# 01_ZYNQ_DDR.net
KiCad netlist of a schematic drawn in Altium Designer
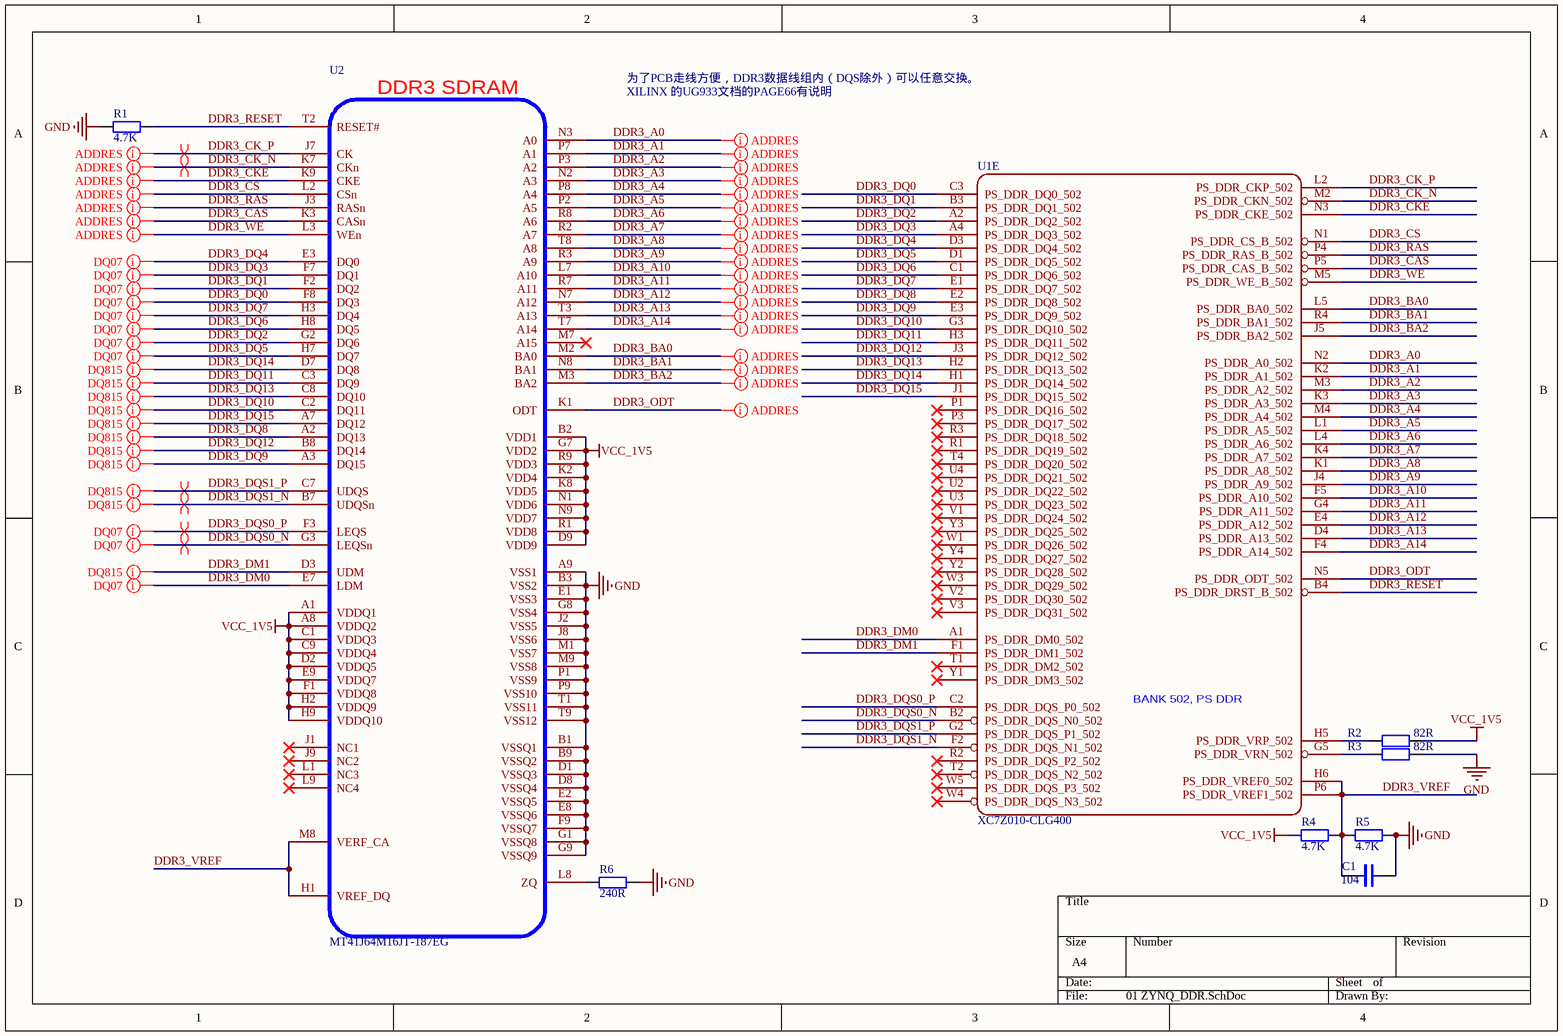
[diagram p0: 01 ZYNQ_DDR.SchDoc]

(export (version "E")
  (design (tool "Eeschema 10.0.6"))
  (components
    (comp (ref "C1")
      (value "104")
      (footprint "LC-0402_C")
      (description "Capacitor")
      (libsource (lib "General") (part "CAP"))
    )
    (comp (ref "R1")
      (value "4.7K")
      (footprint "LC-0402_R")
      (description "Resistor")
      (libsource (lib "General") (part "RES"))
    )
    (comp (ref "R2")
      (value "82R")
      (footprint "LC-0402_R")
      (description "Resistor")
      (libsource (lib "General") (part "RES"))
    )
    (comp (ref "R3")
      (value "82R")
      (footprint "LC-0402_R")
      (description "Resistor")
      (libsource (lib "General") (part "RES"))
    )
    (comp (ref "R4")
      (value "4.7K")
      (footprint "LC-0402_R")
      (description "Resistor")
      (libsource (lib "General") (part "RES"))
    )
    (comp (ref "R5")
      (value "4.7K")
      (footprint "LC-0402_R")
      (description "Resistor")
      (libsource (lib "General") (part "RES"))
    )
    (comp (ref "R6")
      (value "240R")
      (footprint "LC-0402_R")
      (description "Resistor")
      (libsource (lib "") (part "RES_1"))
    )
    (comp (ref "U1")
      (value "XC7Z010-CLG400")
      (footprint "CLG400-0.8")
      (libsource (lib "DDR3_xc7z010-clg400") (part "XC7Z010-CLG400"))
    )
    (comp (ref "U2")
      (value "MT41J64M16JT-187EG")
      (footprint "FBGA96")
      (libsource (lib "DDR3_xc7z010-clg400") (part "DDR3"))
    )
  )
  (nets
    (net (code "1") (name "/DDR3_A0") (class "Default")
      (node (ref "U1") (pin "N2") (pinfunction "PS_DDR_A0_502_N2") (pintype "passive"))
      (node (ref "U2") (pin "N3") (pinfunction "A0_N3") (pintype "passive"))
    )
    (net (code "2") (name "/DDR3_A1") (class "Default")
      (node (ref "U1") (pin "K2") (pinfunction "PS_DDR_A1_502_K2") (pintype "passive"))
      (node (ref "U2") (pin "P7") (pinfunction "A1_P7") (pintype "passive"))
    )
    (net (code "3") (name "/DDR3_A2") (class "Default")
      (node (ref "U1") (pin "M3") (pinfunction "PS_DDR_A2_502_M3") (pintype "passive"))
      (node (ref "U2") (pin "P3") (pinfunction "A2_P3") (pintype "passive"))
    )
    (net (code "4") (name "/DDR3_A3") (class "Default")
      (node (ref "U1") (pin "K3") (pinfunction "PS_DDR_A3_502_K3") (pintype "passive"))
      (node (ref "U2") (pin "N2") (pinfunction "A3_N2") (pintype "passive"))
    )
    (net (code "5") (name "/DDR3_A4") (class "Default")
      (node (ref "U1") (pin "M4") (pinfunction "PS_DDR_A4_502_M4") (pintype "passive"))
      (node (ref "U2") (pin "P8") (pinfunction "A4_P8") (pintype "passive"))
    )
    (net (code "6") (name "/DDR3_A5") (class "Default")
      (node (ref "U1") (pin "L1") (pinfunction "PS_DDR_A5_502_L1") (pintype "passive"))
      (node (ref "U2") (pin "P2") (pinfunction "A5_P2") (pintype "passive"))
    )
    (net (code "7") (name "/DDR3_A6") (class "Default")
      (node (ref "U1") (pin "L4") (pinfunction "PS_DDR_A6_502_L4") (pintype "passive"))
      (node (ref "U2") (pin "R8") (pinfunction "A6_R8") (pintype "passive"))
    )
    (net (code "8") (name "/DDR3_A7") (class "Default")
      (node (ref "U1") (pin "K4") (pinfunction "PS_DDR_A7_502_K4") (pintype "passive"))
      (node (ref "U2") (pin "R2") (pinfunction "A7_R2") (pintype "passive"))
    )
    (net (code "9") (name "/DDR3_A8") (class "Default")
      (node (ref "U1") (pin "K1") (pinfunction "PS_DDR_A8_502_K1") (pintype "passive"))
      (node (ref "U2") (pin "T8") (pinfunction "A8_T8") (pintype "passive"))
    )
    (net (code "10") (name "/DDR3_A9") (class "Default")
      (node (ref "U1") (pin "J4") (pinfunction "PS_DDR_A9_502_J4") (pintype "passive"))
      (node (ref "U2") (pin "R3") (pinfunction "A9_R3") (pintype "passive"))
    )
    (net (code "11") (name "/DDR3_A10") (class "Default")
      (node (ref "U1") (pin "F5") (pinfunction "PS_DDR_A10_502_F5") (pintype "passive"))
      (node (ref "U2") (pin "L7") (pinfunction "A10_L7") (pintype "passive"))
    )
    (net (code "12") (name "/DDR3_A11") (class "Default")
      (node (ref "U1") (pin "G4") (pinfunction "PS_DDR_A11_502_G4") (pintype "passive"))
      (node (ref "U2") (pin "R7") (pinfunction "A11_R7") (pintype "passive"))
    )
    (net (code "13") (name "/DDR3_A12") (class "Default")
      (node (ref "U1") (pin "E4") (pinfunction "PS_DDR_A12_502_E4") (pintype "passive"))
      (node (ref "U2") (pin "N7") (pinfunction "A12_N7") (pintype "passive"))
    )
    (net (code "14") (name "/DDR3_A13") (class "Default")
      (node (ref "U1") (pin "D4") (pinfunction "PS_DDR_A13_502_D4") (pintype "passive"))
      (node (ref "U2") (pin "T3") (pinfunction "A13_T3") (pintype "passive"))
    )
    (net (code "15") (name "/DDR3_A14") (class "Default")
      (node (ref "U1") (pin "F4") (pinfunction "PS_DDR_A14_502_F4") (pintype "passive"))
      (node (ref "U2") (pin "T7") (pinfunction "A14_T7") (pintype "passive"))
    )
    (net (code "16") (name "/DDR3_BA0") (class "Default")
      (node (ref "U1") (pin "L5") (pinfunction "PS_DDR_BA0_502_L5") (pintype "passive"))
      (node (ref "U2") (pin "M2") (pinfunction "BA0_M2") (pintype "passive"))
    )
    (net (code "17") (name "/DDR3_BA1") (class "Default")
      (node (ref "U1") (pin "R4") (pinfunction "PS_DDR_BA1_502_R4") (pintype "passive"))
      (node (ref "U2") (pin "N8") (pinfunction "BA1_N8") (pintype "passive"))
    )
    (net (code "18") (name "/DDR3_BA2") (class "Default")
      (node (ref "U1") (pin "J5") (pinfunction "PS_DDR_BA2_502_J5") (pintype "passive"))
      (node (ref "U2") (pin "M3") (pinfunction "BA2_M3") (pintype "passive"))
    )
    (net (code "19") (name "/DDR3_CAS") (class "Default")
      (node (ref "U1") (pin "P5") (pinfunction "PS_DDR_CAS_B_502_P5") (pintype "passive"))
      (node (ref "U2") (pin "K3") (pinfunction "CASn_K3") (pintype "passive"))
    )
    (net (code "20") (name "/DDR3_CKE") (class "Default")
      (node (ref "U1") (pin "N3") (pinfunction "PS_DDR_CKE_502_N3") (pintype "passive"))
      (node (ref "U2") (pin "K9") (pinfunction "CKE_K9") (pintype "passive"))
    )
    (net (code "21") (name "/DDR3_CK_N") (class "Default")
      (node (ref "U1") (pin "M2") (pinfunction "PS_DDR_CKN_502_M2") (pintype "passive"))
      (node (ref "U2") (pin "K7") (pinfunction "CKn_K7") (pintype "passive"))
    )
    (net (code "22") (name "/DDR3_CK_P") (class "Default")
      (node (ref "U1") (pin "L2") (pinfunction "PS_DDR_CKP_502_L2") (pintype "passive"))
      (node (ref "U2") (pin "J7") (pinfunction "CK_J7") (pintype "passive"))
    )
    (net (code "23") (name "/DDR3_CS") (class "Default")
      (node (ref "U1") (pin "N1") (pinfunction "PS_DDR_CS_B_502_N1") (pintype "passive"))
      (node (ref "U2") (pin "L2") (pinfunction "CSn_L2") (pintype "passive"))
    )
    (net (code "24") (name "/DDR3_DM0") (class "Default")
      (node (ref "U1") (pin "A1") (pinfunction "PS_DDR_DM0_502_A1") (pintype "passive"))
      (node (ref "U2") (pin "E7") (pinfunction "LDM_E7") (pintype "passive"))
    )
    (net (code "25") (name "/DDR3_DM1") (class "Default")
      (node (ref "U1") (pin "F1") (pinfunction "PS_DDR_DM1_502_F1") (pintype "passive"))
      (node (ref "U2") (pin "D3") (pinfunction "UDM_D3") (pintype "passive"))
    )
    (net (code "26") (name "/DDR3_DQ0") (class "Default")
      (node (ref "U1") (pin "C3") (pinfunction "PS_DDR_DQ0_502_C3") (pintype "passive"))
      (node (ref "U2") (pin "F8") (pinfunction "DQ3_F8") (pintype "passive"))
    )
    (net (code "27") (name "/DDR3_DQ1") (class "Default")
      (node (ref "U1") (pin "B3") (pinfunction "PS_DDR_DQ1_502_B3") (pintype "passive"))
      (node (ref "U2") (pin "F2") (pinfunction "DQ2_F2") (pintype "passive"))
    )
    (net (code "28") (name "/DDR3_DQ2") (class "Default")
      (node (ref "U1") (pin "A2") (pinfunction "PS_DDR_DQ2_502_A2") (pintype "passive"))
      (node (ref "U2") (pin "G2") (pinfunction "DQ6_G2") (pintype "passive"))
    )
    (net (code "29") (name "/DDR3_DQ3") (class "Default")
      (node (ref "U1") (pin "A4") (pinfunction "PS_DDR_DQ3_502_A4") (pintype "passive"))
      (node (ref "U2") (pin "F7") (pinfunction "DQ1_F7") (pintype "passive"))
    )
    (net (code "30") (name "/DDR3_DQ4") (class "Default")
      (node (ref "U1") (pin "D3") (pinfunction "PS_DDR_DQ4_502_D3") (pintype "passive"))
      (node (ref "U2") (pin "E3") (pinfunction "DQ0_E3") (pintype "passive"))
    )
    (net (code "31") (name "/DDR3_DQ5") (class "Default")
      (node (ref "U1") (pin "D1") (pinfunction "PS_DDR_DQ5_502_D1") (pintype "passive"))
      (node (ref "U2") (pin "H7") (pinfunction "DQ7_H7") (pintype "passive"))
    )
    (net (code "32") (name "/DDR3_DQ6") (class "Default")
      (node (ref "U1") (pin "C1") (pinfunction "PS_DDR_DQ6_502_C1") (pintype "passive"))
      (node (ref "U2") (pin "H8") (pinfunction "DQ5_H8") (pintype "passive"))
    )
    (net (code "33") (name "/DDR3_DQ7") (class "Default")
      (node (ref "U1") (pin "E1") (pinfunction "PS_DDR_DQ7_502_E1") (pintype "passive"))
      (node (ref "U2") (pin "H3") (pinfunction "DQ4_H3") (pintype "passive"))
    )
    (net (code "34") (name "/DDR3_DQ8") (class "Default")
      (node (ref "U1") (pin "E2") (pinfunction "PS_DDR_DQ8_502_E2") (pintype "passive"))
      (node (ref "U2") (pin "A2") (pinfunction "DQ13_A2") (pintype "passive"))
    )
    (net (code "35") (name "/DDR3_DQ9") (class "Default")
      (node (ref "U1") (pin "E3") (pinfunction "PS_DDR_DQ9_502_E3") (pintype "passive"))
      (node (ref "U2") (pin "A3") (pinfunction "DQ15_A3") (pintype "passive"))
    )
    (net (code "36") (name "/DDR3_DQ10") (class "Default")
      (node (ref "U1") (pin "G3") (pinfunction "PS_DDR_DQ10_502_G3") (pintype "passive"))
      (node (ref "U2") (pin "C2") (pinfunction "DQ11_C2") (pintype "passive"))
    )
    (net (code "37") (name "/DDR3_DQ11") (class "Default")
      (node (ref "U1") (pin "H3") (pinfunction "PS_DDR_DQ11_502_H3") (pintype "passive"))
      (node (ref "U2") (pin "C3") (pinfunction "DQ9_C3") (pintype "passive"))
    )
    (net (code "38") (name "/DDR3_DQ12") (class "Default")
      (node (ref "U1") (pin "J3") (pinfunction "PS_DDR_DQ12_502_J3") (pintype "passive"))
      (node (ref "U2") (pin "B8") (pinfunction "DQ14_B8") (pintype "passive"))
    )
    (net (code "39") (name "/DDR3_DQ13") (class "Default")
      (node (ref "U1") (pin "H2") (pinfunction "PS_DDR_DQ13_502_H2") (pintype "passive"))
      (node (ref "U2") (pin "C8") (pinfunction "DQ10_C8") (pintype "passive"))
    )
    (net (code "40") (name "/DDR3_DQ14") (class "Default")
      (node (ref "U1") (pin "H1") (pinfunction "PS_DDR_DQ14_502_H1") (pintype "passive"))
      (node (ref "U2") (pin "D7") (pinfunction "DQ8_D7") (pintype "passive"))
    )
    (net (code "41") (name "/DDR3_DQ15") (class "Default")
      (node (ref "U1") (pin "J1") (pinfunction "PS_DDR_DQ15_502_J1") (pintype "passive"))
      (node (ref "U2") (pin "A7") (pinfunction "DQ12_A7") (pintype "passive"))
    )
    (net (code "42") (name "/DDR3_DQS0_N") (class "Default")
      (node (ref "U1") (pin "B2") (pinfunction "PS_DDR_DQS_N0_502_B2") (pintype "passive"))
      (node (ref "U2") (pin "G3") (pinfunction "LEQSn_G3") (pintype "passive"))
    )
    (net (code "43") (name "/DDR3_DQS0_P") (class "Default")
      (node (ref "U1") (pin "C2") (pinfunction "PS_DDR_DQS_P0_502_C2") (pintype "passive"))
      (node (ref "U2") (pin "F3") (pinfunction "LEQS_F3") (pintype "passive"))
    )
    (net (code "44") (name "/DDR3_DQS1_N") (class "Default")
      (node (ref "U1") (pin "F2") (pinfunction "PS_DDR_DQS_N1_502_F2") (pintype "passive"))
      (node (ref "U2") (pin "B7") (pinfunction "UDQSn_B7") (pintype "passive"))
    )
    (net (code "45") (name "/DDR3_DQS1_P") (class "Default")
      (node (ref "U1") (pin "G2") (pinfunction "PS_DDR_DQS_P1_502_G2") (pintype "passive"))
      (node (ref "U2") (pin "C7") (pinfunction "UDQS_C7") (pintype "passive"))
    )
    (net (code "46") (name "/DDR3_ODT") (class "Default")
      (node (ref "U1") (pin "N5") (pinfunction "PS_DDR_ODT_502_N5") (pintype "passive"))
      (node (ref "U2") (pin "K1") (pinfunction "ODT_K1") (pintype "passive"))
    )
    (net (code "47") (name "/DDR3_RAS") (class "Default")
      (node (ref "U1") (pin "P4") (pinfunction "PS_DDR_RAS_B_502_P4") (pintype "passive"))
      (node (ref "U2") (pin "J3") (pinfunction "RASn_J3") (pintype "passive"))
    )
    (net (code "48") (name "/DDR3_RESET") (class "Default")
      (node (ref "R1") (pin "1") (pinfunction "1_1") (pintype "passive"))
      (node (ref "U1") (pin "B4") (pinfunction "PS_DDR_DRST_B_502_B4") (pintype "passive"))
      (node (ref "U2") (pin "T2") (pinfunction "RESET#_T2") (pintype "passive"))
    )
    (net (code "49") (name "/DDR3_VREF") (class "Default")
      (node (ref "C1") (pin "1") (pinfunction "1_1") (pintype "passive"))
      (node (ref "R4") (pin "1") (pinfunction "1_1") (pintype "passive"))
      (node (ref "R5") (pin "2") (pinfunction "2_2") (pintype "passive"))
      (node (ref "U1") (pin "H6") (pinfunction "PS_DDR_VREF0_502_H6") (pintype "passive"))
      (node (ref "U1") (pin "P6") (pinfunction "PS_DDR_VREF1_502_P6") (pintype "passive"))
      (node (ref "U2") (pin "H1") (pinfunction "VREF_DQ_H1") (pintype "passive"))
      (node (ref "U2") (pin "M8") (pinfunction "VERF_CA_M8") (pintype "passive"))
    )
    (net (code "50") (name "/DDR3_WE") (class "Default")
      (node (ref "U1") (pin "M5") (pinfunction "PS_DDR_WE_B_502_M5") (pintype "passive"))
      (node (ref "U2") (pin "L3") (pinfunction "WEn_L3") (pintype "passive"))
    )
    (net (code "51") (name "GND") (class "Default")
      (node (ref "C1") (pin "2") (pinfunction "2_2") (pintype "passive"))
      (node (ref "R1") (pin "2") (pinfunction "2_2") (pintype "passive"))
      (node (ref "R3") (pin "1") (pinfunction "1_1") (pintype "passive"))
      (node (ref "R5") (pin "1") (pinfunction "1_1") (pintype "passive"))
      (node (ref "R6") (pin "2") (pinfunction "2_2") (pintype "passive"))
      (node (ref "U2") (pin "A9") (pinfunction "VSS1_A9") (pintype "passive"))
      (node (ref "U2") (pin "B1") (pinfunction "VSSQ1_B1") (pintype "passive"))
      (node (ref "U2") (pin "B3") (pinfunction "VSS2_B3") (pintype "passive"))
      (node (ref "U2") (pin "B9") (pinfunction "VSSQ2_B9") (pintype "passive"))
      (node (ref "U2") (pin "D1") (pinfunction "VSSQ3_D1") (pintype "passive"))
      (node (ref "U2") (pin "D8") (pinfunction "VSSQ4_D8") (pintype "passive"))
      (node (ref "U2") (pin "E1") (pinfunction "VSS3_E1") (pintype "passive"))
      (node (ref "U2") (pin "E2") (pinfunction "VSSQ5_E2") (pintype "passive"))
      (node (ref "U2") (pin "E8") (pinfunction "VSSQ6_E8") (pintype "passive"))
      (node (ref "U2") (pin "F9") (pinfunction "VSSQ7_F9") (pintype "passive"))
      (node (ref "U2") (pin "G1") (pinfunction "VSSQ8_G1") (pintype "passive"))
      (node (ref "U2") (pin "G8") (pinfunction "VSS4_G8") (pintype "passive"))
      (node (ref "U2") (pin "G9") (pinfunction "VSSQ9_G9") (pintype "passive"))
      (node (ref "U2") (pin "J2") (pinfunction "VSS5_J2") (pintype "passive"))
      (node (ref "U2") (pin "J8") (pinfunction "VSS6_J8") (pintype "passive"))
      (node (ref "U2") (pin "M1") (pinfunction "VSS7_M1") (pintype "passive"))
      (node (ref "U2") (pin "M9") (pinfunction "VSS8_M9") (pintype "passive"))
      (node (ref "U2") (pin "P1") (pinfunction "VSS9_P1") (pintype "passive"))
      (node (ref "U2") (pin "P9") (pinfunction "VSS10_P9") (pintype "passive"))
      (node (ref "U2") (pin "T1") (pinfunction "VSS11_T1") (pintype "passive"))
      (node (ref "U2") (pin "T9") (pinfunction "VSS12_T9") (pintype "passive"))
    )
    (net (code "52") (name "Net-(U1E-PS_DDR_VRN_502)") (class "Default")
      (node (ref "R3") (pin "2") (pinfunction "2_2") (pintype "passive"))
      (node (ref "U1") (pin "G5") (pinfunction "PS_DDR_VRN_502_G5") (pintype "passive"))
    )
    (net (code "53") (name "Net-(U1E-PS_DDR_VRP_502)") (class "Default")
      (node (ref "R2") (pin "2") (pinfunction "2_2") (pintype "passive"))
      (node (ref "U1") (pin "H5") (pinfunction "PS_DDR_VRP_502_H5") (pintype "passive"))
    )
    (net (code "54") (name "Net-(U2-ZQ)") (class "Default")
      (node (ref "R6") (pin "1") (pinfunction "1_1") (pintype "passive"))
      (node (ref "U2") (pin "L8") (pinfunction "ZQ_L8") (pintype "passive"))
    )
    (net (code "55") (name "VCC_1V5") (class "Default")
      (node (ref "R2") (pin "1") (pinfunction "1_1") (pintype "passive"))
      (node (ref "R4") (pin "2") (pinfunction "2_2") (pintype "passive"))
      (node (ref "U2") (pin "A1") (pinfunction "VDDQ1_A1") (pintype "passive"))
      (node (ref "U2") (pin "A8") (pinfunction "VDDQ2_A8") (pintype "passive"))
      (node (ref "U2") (pin "B2") (pinfunction "VDD1_B2") (pintype "passive"))
      (node (ref "U2") (pin "C1") (pinfunction "VDDQ3_C1") (pintype "passive"))
      (node (ref "U2") (pin "C9") (pinfunction "VDDQ4_C9") (pintype "passive"))
      (node (ref "U2") (pin "D2") (pinfunction "VDDQ5_D2") (pintype "passive"))
      (node (ref "U2") (pin "D9") (pinfunction "VDD9_D9") (pintype "passive"))
      (node (ref "U2") (pin "E9") (pinfunction "VDDQ7_E9") (pintype "passive"))
      (node (ref "U2") (pin "F1") (pinfunction "VDDQ8_F1") (pintype "passive"))
      (node (ref "U2") (pin "G7") (pinfunction "VDD2_G7") (pintype "passive"))
      (node (ref "U2") (pin "H2") (pinfunction "VDDQ9_H2") (pintype "passive"))
      (node (ref "U2") (pin "H9") (pinfunction "VDDQ10_H9") (pintype "passive"))
      (node (ref "U2") (pin "K2") (pinfunction "VDD4_K2") (pintype "passive"))
      (node (ref "U2") (pin "K8") (pinfunction "VDD5_K8") (pintype "passive"))
      (node (ref "U2") (pin "N1") (pinfunction "VDD6_N1") (pintype "passive"))
      (node (ref "U2") (pin "N9") (pinfunction "VDD7_N9") (pintype "passive"))
      (node (ref "U2") (pin "R1") (pinfunction "VDD8_R1") (pintype "passive"))
      (node (ref "U2") (pin "R9") (pinfunction "VDD3_R9") (pintype "passive"))
    )
    (net (code "56") (name "unconnected-(U1E-PS_DDR_DM2_502-PadT1)") (class "Default")
      (node (ref "U1") (pin "T1") (pinfunction "PS_DDR_DM2_502_T1") (pintype "passive+no_connect"))
    )
    (net (code "57") (name "unconnected-(U1E-PS_DDR_DM3_502-PadY1)") (class "Default")
      (node (ref "U1") (pin "Y1") (pinfunction "PS_DDR_DM3_502_Y1") (pintype "passive+no_connect"))
    )
    (net (code "58") (name "unconnected-(U1E-PS_DDR_DQ16_502-PadP1)") (class "Default")
      (node (ref "U1") (pin "P1") (pinfunction "PS_DDR_DQ16_502_P1") (pintype "passive+no_connect"))
    )
    (net (code "59") (name "unconnected-(U1E-PS_DDR_DQ17_502-PadP3)") (class "Default")
      (node (ref "U1") (pin "P3") (pinfunction "PS_DDR_DQ17_502_P3") (pintype "passive+no_connect"))
    )
    (net (code "60") (name "unconnected-(U1E-PS_DDR_DQ18_502-PadR3)") (class "Default")
      (node (ref "U1") (pin "R3") (pinfunction "PS_DDR_DQ18_502_R3") (pintype "passive+no_connect"))
    )
    (net (code "61") (name "unconnected-(U1E-PS_DDR_DQ19_502-PadR1)") (class "Default")
      (node (ref "U1") (pin "R1") (pinfunction "PS_DDR_DQ19_502_R1") (pintype "passive+no_connect"))
    )
    (net (code "62") (name "unconnected-(U1E-PS_DDR_DQ20_502-PadT4)") (class "Default")
      (node (ref "U1") (pin "T4") (pinfunction "PS_DDR_DQ20_502_T4") (pintype "passive+no_connect"))
    )
    (net (code "63") (name "unconnected-(U1E-PS_DDR_DQ21_502-PadU4)") (class "Default")
      (node (ref "U1") (pin "U4") (pinfunction "PS_DDR_DQ21_502_U4") (pintype "passive+no_connect"))
    )
    (net (code "64") (name "unconnected-(U1E-PS_DDR_DQ22_502-PadU2)") (class "Default")
      (node (ref "U1") (pin "U2") (pinfunction "PS_DDR_DQ22_502_U2") (pintype "passive+no_connect"))
    )
    (net (code "65") (name "unconnected-(U1E-PS_DDR_DQ23_502-PadU3)") (class "Default")
      (node (ref "U1") (pin "U3") (pinfunction "PS_DDR_DQ23_502_U3") (pintype "passive+no_connect"))
    )
    (net (code "66") (name "unconnected-(U1E-PS_DDR_DQ24_502-PadV1)") (class "Default")
      (node (ref "U1") (pin "V1") (pinfunction "PS_DDR_DQ24_502_V1") (pintype "passive+no_connect"))
    )
    (net (code "67") (name "unconnected-(U1E-PS_DDR_DQ25_502-PadY3)") (class "Default")
      (node (ref "U1") (pin "Y3") (pinfunction "PS_DDR_DQ25_502_Y3") (pintype "passive+no_connect"))
    )
    (net (code "68") (name "unconnected-(U1E-PS_DDR_DQ26_502-PadW1)") (class "Default")
      (node (ref "U1") (pin "W1") (pinfunction "PS_DDR_DQ26_502_W1") (pintype "passive+no_connect"))
    )
    (net (code "69") (name "unconnected-(U1E-PS_DDR_DQ27_502-PadY4)") (class "Default")
      (node (ref "U1") (pin "Y4") (pinfunction "PS_DDR_DQ27_502_Y4") (pintype "passive+no_connect"))
    )
    (net (code "70") (name "unconnected-(U1E-PS_DDR_DQ28_502-PadY2)") (class "Default")
      (node (ref "U1") (pin "Y2") (pinfunction "PS_DDR_DQ28_502_Y2") (pintype "passive+no_connect"))
    )
    (net (code "71") (name "unconnected-(U1E-PS_DDR_DQ29_502-PadW3)") (class "Default")
      (node (ref "U1") (pin "W3") (pinfunction "PS_DDR_DQ29_502_W3") (pintype "passive+no_connect"))
    )
    (net (code "72") (name "unconnected-(U1E-PS_DDR_DQ30_502-PadV2)") (class "Default")
      (node (ref "U1") (pin "V2") (pinfunction "PS_DDR_DQ30_502_V2") (pintype "passive+no_connect"))
    )
    (net (code "73") (name "unconnected-(U1E-PS_DDR_DQ31_502-PadV3)") (class "Default")
      (node (ref "U1") (pin "V3") (pinfunction "PS_DDR_DQ31_502_V3") (pintype "passive+no_connect"))
    )
    (net (code "74") (name "unconnected-(U1E-PS_DDR_DQS_N2_502-PadT2)") (class "Default")
      (node (ref "U1") (pin "T2") (pinfunction "PS_DDR_DQS_N2_502_T2") (pintype "passive+no_connect"))
    )
    (net (code "75") (name "unconnected-(U1E-PS_DDR_DQS_N3_502-PadW4)") (class "Default")
      (node (ref "U1") (pin "W4") (pinfunction "PS_DDR_DQS_N3_502_W4") (pintype "passive+no_connect"))
    )
    (net (code "76") (name "unconnected-(U1E-PS_DDR_DQS_P2_502-PadR2)") (class "Default")
      (node (ref "U1") (pin "R2") (pinfunction "PS_DDR_DQS_P2_502_R2") (pintype "passive+no_connect"))
    )
    (net (code "77") (name "unconnected-(U1E-PS_DDR_DQS_P3_502-PadW5)") (class "Default")
      (node (ref "U1") (pin "W5") (pinfunction "PS_DDR_DQS_P3_502_W5") (pintype "passive+no_connect"))
    )
    (net (code "78") (name "unconnected-(U2-A15-PadM7)") (class "Default")
      (node (ref "U2") (pin "M7") (pinfunction "A15_M7") (pintype "passive+no_connect"))
    )
    (net (code "79") (name "unconnected-(U2-NC1-PadJ1)") (class "Default")
      (node (ref "U2") (pin "J1") (pinfunction "NC1_J1") (pintype "passive+no_connect"))
    )
    (net (code "80") (name "unconnected-(U2-NC2-PadJ9)") (class "Default")
      (node (ref "U2") (pin "J9") (pinfunction "NC2_J9") (pintype "passive+no_connect"))
    )
    (net (code "81") (name "unconnected-(U2-NC3-PadL1)") (class "Default")
      (node (ref "U2") (pin "L1") (pinfunction "NC3_L1") (pintype "passive+no_connect"))
    )
    (net (code "82") (name "unconnected-(U2-NC4-PadL9)") (class "Default")
      (node (ref "U2") (pin "L9") (pinfunction "NC4_L9") (pintype "passive+no_connect"))
    )
  )
)
